# mcu.net
KiCad netlist of a schematic drawn in Altium Designer
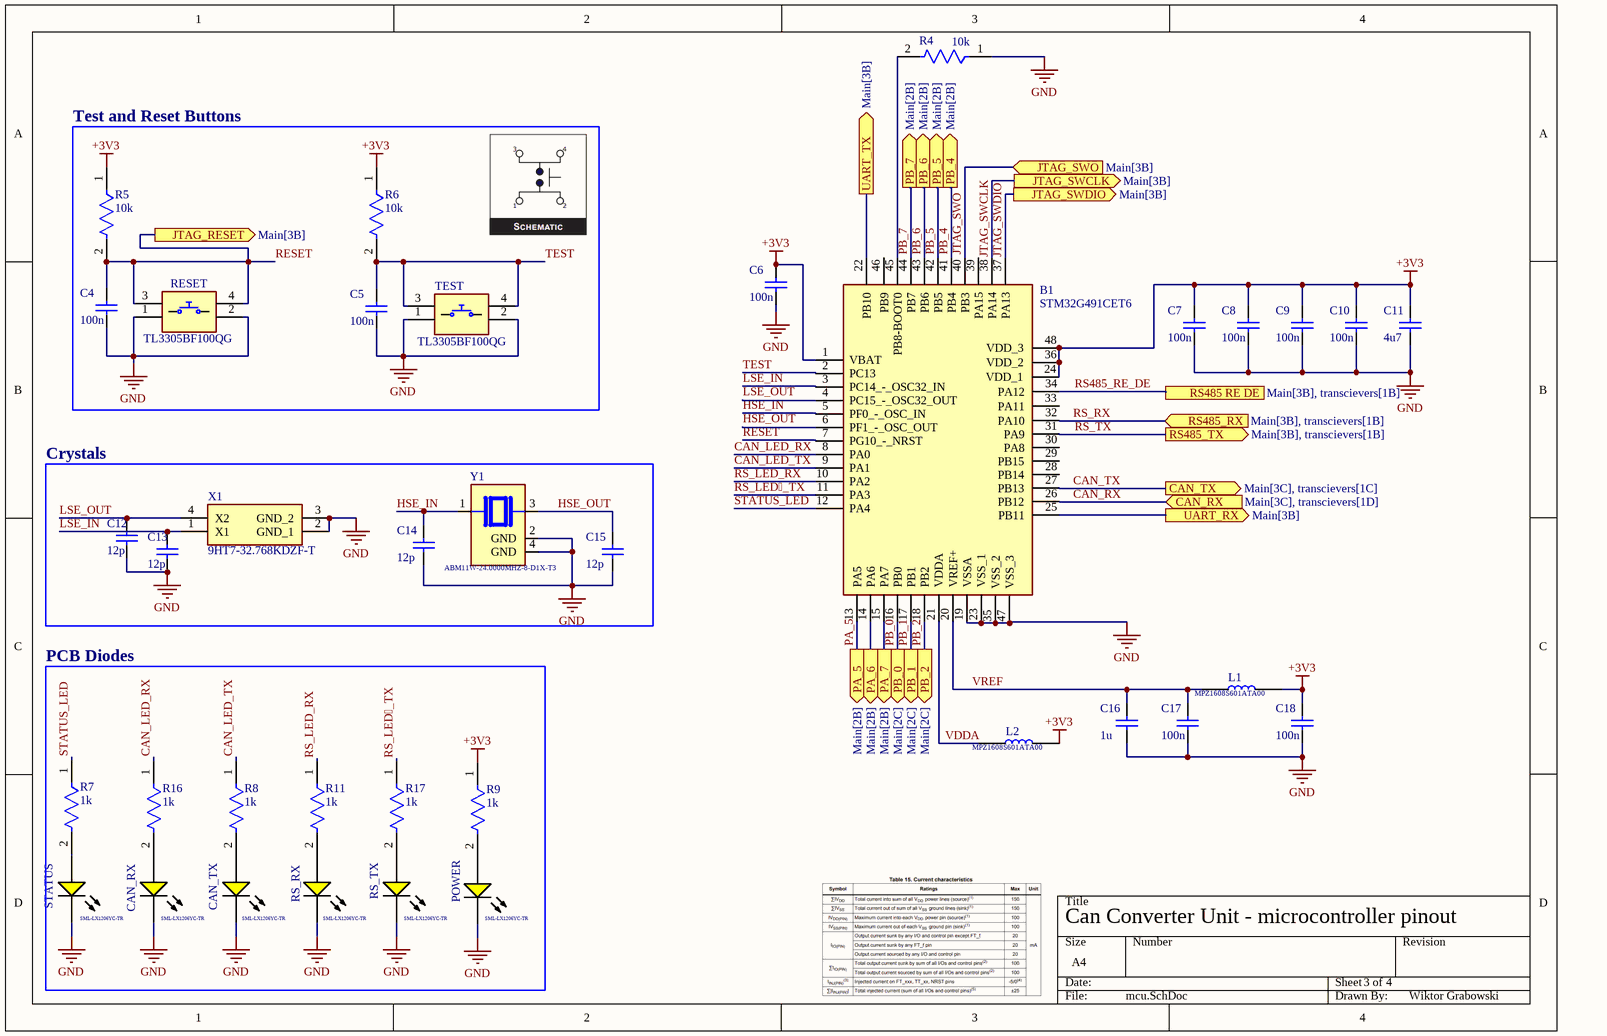
[diagram p0: mcu.SchDoc]

(export (version "E")
  (design (tool "Eeschema 10.0.6"))
  (components
    (comp (ref "B1")
      (value "STM32G491CET6")
      (footprint "STM32G491CET6")
      (description "ARM Microcontrollers - MCU Mainstream Arm Cortex-M4+ MCU 170MHz with 512Kbytes of Flash memory")
      (fields (field (name "MOUSER PART NUMBER") "511-STM32G491CET6"))
      (libsource (lib "HydrogreenLibrary") (part "STM32G491CET6"))
    )
    (comp (ref "C4")
      (value "100n")
      (footprint "CAPC1206(3216)170_M")
      (description "CAP 47nF 200V ±10% 1206 (3216 Metric) Thickness 1.7mm SMD")
      (fields (field (name "TOLERANCE") "Â±10%"))
      (libsource (lib "Altium Content Vault") (part "CAP"))
    )
    (comp (ref "C5")
      (value "100n")
      (footprint "CAPC1206(3216)170_M")
      (description "CAP 47nF 200V ±10% 1206 (3216 Metric) Thickness 1.7mm SMD")
      (fields (field (name "TOLERANCE") "Â±10%"))
      (libsource (lib "Altium Content Vault") (part "CAP"))
    )
    (comp (ref "C6")
      (value "100n")
      (footprint "CAPC1206(3216)170_M")
      (description "CAP 47nF 200V ±10% 1206 (3216 Metric) Thickness 1.7mm SMD")
      (fields (field (name "TOLERANCE") "Â±10%"))
      (libsource (lib "Altium Content Vault") (part "CAP"))
    )
    (comp (ref "C7")
      (value "100n")
      (footprint "CAPC1206(3216)170_M")
      (description "CAP 47nF 200V ±10% 1206 (3216 Metric) Thickness 1.7mm SMD")
      (fields (field (name "TOLERANCE") "Â±10%"))
      (libsource (lib "Altium Content Vault") (part "CAP"))
    )
    (comp (ref "C8")
      (value "100n")
      (footprint "CAPC1206(3216)170_M")
      (description "CAP 47nF 200V ±10% 1206 (3216 Metric) Thickness 1.7mm SMD")
      (fields (field (name "TOLERANCE") "Â±10%"))
      (libsource (lib "Altium Content Vault") (part "CAP"))
    )
    (comp (ref "C9")
      (value "100n")
      (footprint "CAPC1206(3216)170_M")
      (description "CAP 47nF 200V ±10% 1206 (3216 Metric) Thickness 1.7mm SMD")
      (fields (field (name "TOLERANCE") "Â±10%"))
      (libsource (lib "Altium Content Vault") (part "CAP"))
    )
    (comp (ref "C10")
      (value "100n")
      (footprint "CAPC1206(3216)170_M")
      (description "CAP 47nF 200V ±10% 1206 (3216 Metric) Thickness 1.7mm SMD")
      (fields (field (name "TOLERANCE") "Â±10%"))
      (libsource (lib "Altium Content Vault") (part "CAP"))
    )
    (comp (ref "C11")
      (value "4u7")
      (footprint "CAPC1206(3216)170_M")
      (description "CAP 47nF 200V ±10% 1206 (3216 Metric) Thickness 1.7mm SMD")
      (fields (field (name "TOLERANCE") "Â±10%"))
      (libsource (lib "Altium Content Vault") (part "CAP"))
    )
    (comp (ref "C12")
      (value "12p")
      (footprint "CAPC1206(3216)170_M")
      (description "CAP 47nF 200V ±10% 1206 (3216 Metric) Thickness 1.7mm SMD")
      (fields (field (name "TOLERANCE") "Â±10%"))
      (libsource (lib "Altium Content Vault") (part "CAP"))
    )
    (comp (ref "C13")
      (value "12p")
      (footprint "CAPC1206(3216)170_M")
      (description "CAP 47nF 200V ±10% 1206 (3216 Metric) Thickness 1.7mm SMD")
      (fields (field (name "TOLERANCE") "Â±10%"))
      (libsource (lib "Altium Content Vault") (part "CAP"))
    )
    (comp (ref "C14")
      (value "12p")
      (footprint "CAPC1206(3216)170_M")
      (description "CAP 47nF 200V ±10% 1206 (3216 Metric) Thickness 1.7mm SMD")
      (fields (field (name "TOLERANCE") "Â±10%"))
      (libsource (lib "Altium Content Vault") (part "CAP"))
    )
    (comp (ref "C15")
      (value "12p")
      (footprint "CAPC1206(3216)170_M")
      (description "CAP 47nF 200V ±10% 1206 (3216 Metric) Thickness 1.7mm SMD")
      (fields (field (name "TOLERANCE") "Â±10%"))
      (libsource (lib "Altium Content Vault") (part "CAP"))
    )
    (comp (ref "C16")
      (value "1u")
      (footprint "CAPC1206(3216)170_M")
      (description "CAP 47nF 200V ±10% 1206 (3216 Metric) Thickness 1.7mm SMD")
      (fields (field (name "TOLERANCE") "Â±10%"))
      (libsource (lib "Altium Content Vault") (part "CAP"))
    )
    (comp (ref "C17")
      (value "100n")
      (footprint "CAPC1206(3216)170_M")
      (description "CAP 47nF 200V ±10% 1206 (3216 Metric) Thickness 1.7mm SMD")
      (fields (field (name "TOLERANCE") "Â±10%"))
      (libsource (lib "Altium Content Vault") (part "CAP"))
    )
    (comp (ref "C18")
      (value "100n")
      (footprint "CAPC1206(3216)170_M")
      (description "CAP 47nF 200V ±10% 1206 (3216 Metric) Thickness 1.7mm SMD")
      (fields (field (name "TOLERANCE") "Â±10%"))
      (libsource (lib "Altium Content Vault") (part "CAP"))
    )
    (comp (ref "CAN_RX")
      (value "SML-LX1206YC-TR")
      (footprint "LUMX-SML-LX1206YC-TR_V")
      (description "Yellow LED, Water Clear Len, 585 nm, 2.1 V, -40 to 85 degC, 2-Pin SMD, RoHS, Tape and Reel")
      (fields (field (name "MANUFACTURER") "Lumex"))
      (libsource (lib "Altium Content Vault") (part "LED-YELLOW-AK-2"))
    )
    (comp (ref "CAN_TX")
      (value "SML-LX1206YC-TR")
      (footprint "LUMX-SML-LX1206YC-TR_V")
      (description "Yellow LED, Water Clear Len, 585 nm, 2.1 V, -40 to 85 degC, 2-Pin SMD, RoHS, Tape and Reel")
      (fields (field (name "MANUFACTURER") "Lumex"))
      (libsource (lib "Altium Content Vault") (part "LED-YELLOW-AK-2"))
    )
    (comp (ref "L1")
      (value "MPZ1608S601ATA00")
      (footprint "INDC1608X95N")
      (description "Ferrite Beads Multi-Layer 600Ohm 25% 100MHz 1A 0.15Ohm DCR 0603 T/R")
      (fields (field (name "MF") "TDK") (field (name "TOLERANCE") "25%"))
      (libsource (lib "HydrogreenLibrary") (part "MPZ1608S601ATA00"))
    )
    (comp (ref "L2")
      (value "MPZ1608S601ATA00")
      (footprint "INDC1608X95N")
      (description "Ferrite Beads Multi-Layer 600Ohm 25% 100MHz 1A 0.15Ohm DCR 0603 T/R")
      (fields (field (name "MF") "TDK") (field (name "TOLERANCE") "25%"))
      (libsource (lib "HydrogreenLibrary") (part "MPZ1608S601ATA00"))
    )
    (comp (ref "POWER")
      (value "SML-LX1206YC-TR")
      (footprint "LUMX-SML-LX1206YC-TR_V")
      (description "Yellow LED, Water Clear Len, 585 nm, 2.1 V, -40 to 85 degC, 2-Pin SMD, RoHS, Tape and Reel")
      (fields (field (name "MANUFACTURER") "Lumex"))
      (libsource (lib "Altium Content Vault") (part "LED-YELLOW-AK-2"))
    )
    (comp (ref "R4")
      (value "10k")
      (footprint "FP-RK73H2B-MFG")
      (description "40.2kΩ ±1% 0.25W Chip Resistor 1206 Thick Film AEC-Q200 Qualified")
      (fields (field (name "TOLERANCE") "1%"))
      (libsource (lib "Altium Content Vault") (part "1029c3af85768c4190bb7ad29bc67b5"))
    )
    (comp (ref "R5")
      (value "10k")
      (footprint "FP-RK73H2B-MFG")
      (description "40.2kΩ ±1% 0.25W Chip Resistor 1206 Thick Film AEC-Q200 Qualified")
      (fields (field (name "TOLERANCE") "1%"))
      (libsource (lib "Altium Content Vault") (part "1029c3af85768c4190bb7ad29bc67b5"))
    )
    (comp (ref "R6")
      (value "10k")
      (footprint "FP-RK73H2B-MFG")
      (description "40.2kΩ ±1% 0.25W Chip Resistor 1206 Thick Film AEC-Q200 Qualified")
      (fields (field (name "TOLERANCE") "1%"))
      (libsource (lib "Altium Content Vault") (part "1029c3af85768c4190bb7ad29bc67b5"))
    )
    (comp (ref "R7")
      (value "1k")
      (footprint "FP-RK73H2B-MFG")
      (description "40.2kΩ ±1% 0.25W Chip Resistor 1206 Thick Film AEC-Q200 Qualified")
      (fields (field (name "TOLERANCE") "1%"))
      (libsource (lib "Altium Content Vault") (part "1029c3af85768c4190bb7ad29bc67b5"))
    )
    (comp (ref "R8")
      (value "1k")
      (footprint "FP-RK73H2B-MFG")
      (description "40.2kΩ ±1% 0.25W Chip Resistor 1206 Thick Film AEC-Q200 Qualified")
      (fields (field (name "TOLERANCE") "1%"))
      (libsource (lib "Altium Content Vault") (part "1029c3af85768c4190bb7ad29bc67b5"))
    )
    (comp (ref "R9")
      (value "1k")
      (footprint "FP-RK73H2B-MFG")
      (description "40.2kΩ ±1% 0.25W Chip Resistor 1206 Thick Film AEC-Q200 Qualified")
      (fields (field (name "TOLERANCE") "1%"))
      (libsource (lib "Altium Content Vault") (part "1029c3af85768c4190bb7ad29bc67b5"))
    )
    (comp (ref "R11")
      (value "1k")
      (footprint "FP-RK73H2B-MFG")
      (description "40.2kΩ ±1% 0.25W Chip Resistor 1206 Thick Film AEC-Q200 Qualified")
      (fields (field (name "TOLERANCE") "1%"))
      (libsource (lib "Altium Content Vault") (part "1029c3af85768c4190bb7ad29bc67b5"))
    )
    (comp (ref "R16")
      (value "1k")
      (footprint "FP-RK73H2B-MFG")
      (description "40.2kΩ ±1% 0.25W Chip Resistor 1206 Thick Film AEC-Q200 Qualified")
      (fields (field (name "TOLERANCE") "1%"))
      (libsource (lib "Altium Content Vault") (part "1029c3af85768c4190bb7ad29bc67b5"))
    )
    (comp (ref "R17")
      (value "1k")
      (footprint "FP-RK73H2B-MFG")
      (description "40.2kΩ ±1% 0.25W Chip Resistor 1206 Thick Film AEC-Q200 Qualified")
      (fields (field (name "TOLERANCE") "1%"))
      (libsource (lib "Altium Content Vault") (part "1029c3af85768c4190bb7ad29bc67b5"))
    )
    (comp (ref "RESET")
      (value "TL3305BF100QG")
      (footprint "TL3305BF160QG")
      (description "TL3305 Ultra-Miniature Tact Switch 100gf 5.0mm actuator Silver Contact Gullwing")
      (fields
        (field (name "MOUSER PART NUMBER") "612-TL3305BF100QG")
        (field (name "MANUFACTURER") "E-Switch")
      )
      (libsource (lib "HydrogreenLibrary") (part "TL3305BF100QG"))
    )
    (comp (ref "RS_RX")
      (value "SML-LX1206YC-TR")
      (footprint "LUMX-SML-LX1206YC-TR_V")
      (description "Yellow LED, Water Clear Len, 585 nm, 2.1 V, -40 to 85 degC, 2-Pin SMD, RoHS, Tape and Reel")
      (fields (field (name "MANUFACTURER") "Lumex"))
      (libsource (lib "Altium Content Vault") (part "LED-YELLOW-AK-2"))
    )
    (comp (ref "RS_TX")
      (value "SML-LX1206YC-TR")
      (footprint "LUMX-SML-LX1206YC-TR_V")
      (description "Yellow LED, Water Clear Len, 585 nm, 2.1 V, -40 to 85 degC, 2-Pin SMD, RoHS, Tape and Reel")
      (fields (field (name "MANUFACTURER") "Lumex"))
      (libsource (lib "Altium Content Vault") (part "LED-YELLOW-AK-2"))
    )
    (comp (ref "STATUS")
      (value "SML-LX1206YC-TR")
      (footprint "LUMX-SML-LX1206YC-TR_V")
      (description "Yellow LED, Water Clear Len, 585 nm, 2.1 V, -40 to 85 degC, 2-Pin SMD, RoHS, Tape and Reel")
      (fields (field (name "MANUFACTURER") "Lumex"))
      (libsource (lib "Altium Content Vault") (part "LED-YELLOW-AK-2"))
    )
    (comp (ref "TEST")
      (value "TL3305BF100QG")
      (footprint "TL3305BF160QG")
      (description "TL3305 Ultra-Miniature Tact Switch 100gf 5.0mm actuator Silver Contact Gullwing")
      (fields
        (field (name "MOUSER PART NUMBER") "612-TL3305BF100QG")
        (field (name "MANUFACTURER") "E-Switch")
      )
      (libsource (lib "HydrogreenLibrary") (part "TL3305BF100QG"))
    )
    (comp (ref "X1")
      (value "9HT7-32.768KDZF-T")
      (footprint "9HT732768KDZFT")
      (description "Parallel - Fundamental Quartz Crystal, 0.032768MHz Nom")
      (fields (field (name "MOUSER PART NUMBER") "717-9HT7-32.768KDZFT") (field (name "MANUFACTURER") "TXC"))
      (libsource (lib "HydrogreenLibrary") (part "9HT7-32.768KDZF-T"))
    )
    (comp (ref "Y1")
      (value "ABM11W-24.0000MHZ-8-D1X-T3")
      (footprint "XTAL_ABM11W-24.0000MHZ-8-D1X-T3")
      (description "Crystal, Quartz, 24 MHz, SMD, 2mm x 1.6mm x 0.5mm, 20 ppm, 8 pF, 10 ppm, ABM11W")
      (fields (field (name "MF") "Abracon LLC") (field (name "MANUFACTURER") "Abracon"))
      (libsource (lib "HydrogreenLibrary") (part "ABM11W-24.0000MHZ-8-D1X-T3"))
    )
  )
  (nets
    (net (code "1") (name "+3V3") (class "Default")
      (node (ref "B1") (pin "1") (pinfunction "VBAT_1") (pintype "passive"))
      (node (ref "B1") (pin "24") (pinfunction "VDD_1_24") (pintype "passive"))
      (node (ref "B1") (pin "36") (pinfunction "VDD_2_36") (pintype "passive"))
      (node (ref "B1") (pin "48") (pinfunction "VDD_3_48") (pintype "passive"))
      (node (ref "C10") (pin "2") (pinfunction "2_2") (pintype "passive"))
      (node (ref "C11") (pin "2") (pinfunction "2_2") (pintype "passive"))
      (node (ref "C18") (pin "2") (pinfunction "2_2") (pintype "passive"))
      (node (ref "C6") (pin "2") (pinfunction "2_2") (pintype "passive"))
      (node (ref "C7") (pin "2") (pinfunction "2_2") (pintype "passive"))
      (node (ref "C8") (pin "2") (pinfunction "2_2") (pintype "passive"))
      (node (ref "C9") (pin "2") (pinfunction "2_2") (pintype "passive"))
      (node (ref "L1") (pin "2") (pinfunction "2_2") (pintype "passive"))
      (node (ref "L2") (pin "2") (pinfunction "2_2") (pintype "passive"))
      (node (ref "R5") (pin "1") (pinfunction "1_1") (pintype "passive"))
      (node (ref "R6") (pin "1") (pinfunction "1_1") (pintype "passive"))
      (node (ref "R9") (pin "1") (pinfunction "1_1") (pintype "passive"))
    )
    (net (code "2") (name "/CAN_LED_RX") (class "Default")
      (node (ref "B1") (pin "8") (pinfunction "PA0_8") (pintype "passive"))
      (node (ref "R16") (pin "1") (pinfunction "1_1") (pintype "passive"))
    )
    (net (code "3") (name "/CAN_LED_TX") (class "Default")
      (node (ref "B1") (pin "9") (pinfunction "PA1_9") (pintype "passive"))
      (node (ref "R8") (pin "1") (pinfunction "1_1") (pintype "passive"))
    )
    (net (code "4") (name "/CAN_RX") (class "Default")
      (node (ref "B1") (pin "26") (pinfunction "PB12_26") (pintype "passive"))
    )
    (net (code "5") (name "/CAN_TX") (class "Default")
      (node (ref "B1") (pin "27") (pinfunction "PB13_27") (pintype "passive"))
    )
    (net (code "6") (name "/HSE_IN") (class "Default")
      (node (ref "B1") (pin "5") (pinfunction "PF0_-_OSC_IN_5") (pintype "passive"))
      (node (ref "C14") (pin "2") (pinfunction "2_2") (pintype "passive"))
      (node (ref "Y1") (pin "1") (pinfunction "1_1") (pintype "passive"))
    )
    (net (code "7") (name "/HSE_OUT") (class "Default")
      (node (ref "B1") (pin "6") (pinfunction "PF1_-_OSC_OUT_6") (pintype "passive"))
      (node (ref "C15") (pin "2") (pinfunction "2_2") (pintype "passive"))
      (node (ref "Y1") (pin "3") (pinfunction "2_3") (pintype "passive"))
    )
    (net (code "8") (name "/JTAG_SWCLK") (class "Default")
      (node (ref "B1") (pin "38") (pinfunction "PA14_38") (pintype "passive"))
    )
    (net (code "9") (name "/JTAG_SWDIO") (class "Default")
      (node (ref "B1") (pin "37") (pinfunction "PA13_37") (pintype "passive"))
    )
    (net (code "10") (name "/JTAG_SWO") (class "Default")
      (node (ref "B1") (pin "40") (pinfunction "PB3_40") (pintype "passive"))
    )
    (net (code "11") (name "/LSE_IN") (class "Default")
      (node (ref "B1") (pin "3") (pinfunction "PC14_-_OSC32_IN_3") (pintype "passive"))
      (node (ref "C13") (pin "2") (pinfunction "2_2") (pintype "passive"))
      (node (ref "X1") (pin "1") (pinfunction "X1_1") (pintype "passive"))
    )
    (net (code "12") (name "/LSE_OUT") (class "Default")
      (node (ref "B1") (pin "4") (pinfunction "PC15_-_OSC32_OUT_4") (pintype "passive"))
      (node (ref "C12") (pin "2") (pinfunction "2_2") (pintype "passive"))
      (node (ref "X1") (pin "4") (pinfunction "X2_4") (pintype "passive"))
    )
    (net (code "13") (name "/PA_5") (class "Default")
      (node (ref "B1") (pin "13") (pinfunction "PA5_13") (pintype "passive"))
    )
    (net (code "14") (name "/PA_6") (class "Default")
      (node (ref "B1") (pin "14") (pinfunction "PA6_14") (pintype "passive"))
    )
    (net (code "15") (name "/PA_7") (class "Default")
      (node (ref "B1") (pin "15") (pinfunction "PA7_15") (pintype "passive"))
    )
    (net (code "16") (name "/PB_0") (class "Default")
      (node (ref "B1") (pin "16") (pinfunction "PB0_16") (pintype "passive"))
    )
    (net (code "17") (name "/PB_1") (class "Default")
      (node (ref "B1") (pin "17") (pinfunction "PB1_17") (pintype "passive"))
    )
    (net (code "18") (name "/PB_2") (class "Default")
      (node (ref "B1") (pin "18") (pinfunction "PB2_18") (pintype "passive"))
    )
    (net (code "19") (name "/PB_4") (class "Default")
      (node (ref "B1") (pin "41") (pinfunction "PB4_41") (pintype "passive"))
    )
    (net (code "20") (name "/PB_5") (class "Default")
      (node (ref "B1") (pin "42") (pinfunction "PB5_42") (pintype "passive"))
    )
    (net (code "21") (name "/PB_6") (class "Default")
      (node (ref "B1") (pin "43") (pinfunction "PB6_43") (pintype "passive"))
    )
    (net (code "22") (name "/PB_7") (class "Default")
      (node (ref "B1") (pin "44") (pinfunction "PB7_44") (pintype "passive"))
    )
    (net (code "23") (name "/RESET") (class "Default")
      (node (ref "B1") (pin "7") (pinfunction "PG10_-_NRST_7") (pintype "passive"))
      (node (ref "C4") (pin "2") (pinfunction "2_2") (pintype "passive"))
      (node (ref "R5") (pin "2") (pinfunction "2_2") (pintype "passive"))
      (node (ref "RESET") (pin "3") (pintype "passive"))
      (node (ref "RESET") (pin "4") (pintype "passive"))
    )
    (net (code "24") (name "/RS485_RE_DE") (class "Default")
      (node (ref "B1") (pin "34") (pinfunction "PA12_34") (pintype "passive"))
    )
    (net (code "25") (name "/RS_LED_TX") (class "Default")
      (node (ref "B1") (pin "11") (pinfunction "PA3_11") (pintype "passive"))
      (node (ref "R17") (pin "1") (pinfunction "1_1") (pintype "passive"))
    )
    (net (code "26") (name "/RS_LED_RX") (class "Default")
      (node (ref "B1") (pin "10") (pinfunction "PA2_10") (pintype "passive"))
      (node (ref "R11") (pin "1") (pinfunction "1_1") (pintype "passive"))
    )
    (net (code "27") (name "/RS_RX") (class "Default")
      (node (ref "B1") (pin "32") (pinfunction "PA10_32") (pintype "passive"))
    )
    (net (code "28") (name "/RS_TX") (class "Default")
      (node (ref "B1") (pin "31") (pinfunction "PA9_31") (pintype "passive"))
    )
    (net (code "29") (name "/STATUS_LED") (class "Default")
      (node (ref "B1") (pin "12") (pinfunction "PA4_12") (pintype "passive"))
      (node (ref "R7") (pin "1") (pinfunction "1_1") (pintype "passive"))
    )
    (net (code "30") (name "/TEST") (class "Default")
      (node (ref "B1") (pin "2") (pinfunction "PC13_2") (pintype "passive"))
      (node (ref "C5") (pin "2") (pinfunction "2_2") (pintype "passive"))
      (node (ref "R6") (pin "2") (pinfunction "2_2") (pintype "passive"))
      (node (ref "TEST") (pin "3") (pintype "passive"))
      (node (ref "TEST") (pin "4") (pintype "passive"))
    )
    (net (code "31") (name "/UART_RX") (class "Default")
      (node (ref "B1") (pin "25") (pinfunction "PB11_25") (pintype "passive"))
    )
    (net (code "32") (name "/UART_TX") (class "Default")
      (node (ref "B1") (pin "22") (pinfunction "PB10_22") (pintype "passive"))
    )
    (net (code "33") (name "/VDDA") (class "Default")
      (node (ref "B1") (pin "21") (pinfunction "VDDA_21") (pintype "passive"))
      (node (ref "L2") (pin "1") (pinfunction "1_1") (pintype "passive"))
    )
    (net (code "34") (name "/VREF") (class "Default")
      (node (ref "B1") (pin "20") (pinfunction "VREF+_20") (pintype "passive"))
      (node (ref "C16") (pin "2") (pinfunction "2_2") (pintype "passive"))
      (node (ref "C17") (pin "2") (pinfunction "2_2") (pintype "passive"))
      (node (ref "L1") (pin "1") (pinfunction "1_1") (pintype "passive"))
    )
    (net (code "35") (name "GND") (class "Default")
      (node (ref "B1") (pin "19") (pinfunction "VSSA_19") (pintype "passive"))
      (node (ref "B1") (pin "23") (pinfunction "VSS_1_23") (pintype "passive"))
      (node (ref "B1") (pin "35") (pinfunction "VSS_2_35") (pintype "passive"))
      (node (ref "B1") (pin "47") (pinfunction "VSS_3_47") (pintype "passive"))
      (node (ref "C10") (pin "1") (pinfunction "1_1") (pintype "passive"))
      (node (ref "C11") (pin "1") (pinfunction "1_1") (pintype "passive"))
      (node (ref "C12") (pin "1") (pinfunction "1_1") (pintype "passive"))
      (node (ref "C13") (pin "1") (pinfunction "1_1") (pintype "passive"))
      (node (ref "C14") (pin "1") (pinfunction "1_1") (pintype "passive"))
      (node (ref "C15") (pin "1") (pinfunction "1_1") (pintype "passive"))
      (node (ref "C16") (pin "1") (pinfunction "1_1") (pintype "passive"))
      (node (ref "C17") (pin "1") (pinfunction "1_1") (pintype "passive"))
      (node (ref "C18") (pin "1") (pinfunction "1_1") (pintype "passive"))
      (node (ref "C4") (pin "1") (pinfunction "1_1") (pintype "passive"))
      (node (ref "C5") (pin "1") (pinfunction "1_1") (pintype "passive"))
      (node (ref "C6") (pin "1") (pinfunction "1_1") (pintype "passive"))
      (node (ref "C7") (pin "1") (pinfunction "1_1") (pintype "passive"))
      (node (ref "C8") (pin "1") (pinfunction "1_1") (pintype "passive"))
      (node (ref "C9") (pin "1") (pinfunction "1_1") (pintype "passive"))
      (node (ref "CAN_RX") (pin "2") (pinfunction "K_2") (pintype "passive"))
      (node (ref "CAN_TX") (pin "2") (pinfunction "K_2") (pintype "passive"))
      (node (ref "POWER") (pin "2") (pinfunction "K_2") (pintype "passive"))
      (node (ref "R4") (pin "1") (pinfunction "1_1") (pintype "passive"))
      (node (ref "RESET") (pin "1") (pintype "passive"))
      (node (ref "RESET") (pin "2") (pintype "passive"))
      (node (ref "RS_RX") (pin "2") (pinfunction "K_2") (pintype "passive"))
      (node (ref "RS_TX") (pin "2") (pinfunction "K_2") (pintype "passive"))
      (node (ref "STATUS") (pin "2") (pinfunction "K_2") (pintype "passive"))
      (node (ref "TEST") (pin "1") (pintype "passive"))
      (node (ref "TEST") (pin "2") (pintype "passive"))
      (node (ref "X1") (pin "2") (pinfunction "GND_1_2") (pintype "passive"))
      (node (ref "X1") (pin "3") (pinfunction "GND_2_3") (pintype "passive"))
      (node (ref "Y1") (pin "2") (pinfunction "GND_2") (pintype "power_in"))
      (node (ref "Y1") (pin "4") (pinfunction "GND_4") (pintype "power_in"))
    )
    (net (code "36") (name "Net-(B1-PB8-BOOT0)") (class "Default")
      (node (ref "B1") (pin "45") (pinfunction "PB8-BOOT0_45") (pintype "passive"))
      (node (ref "R4") (pin "2") (pinfunction "2_2") (pintype "passive"))
    )
    (net (code "37") (name "Net-(CAN_RX-A)") (class "Default")
      (node (ref "CAN_RX") (pin "1") (pinfunction "A_1") (pintype "passive"))
      (node (ref "R16") (pin "2") (pinfunction "2_2") (pintype "passive"))
    )
    (net (code "38") (name "Net-(CAN_TX-A)") (class "Default")
      (node (ref "CAN_TX") (pin "1") (pinfunction "A_1") (pintype "passive"))
      (node (ref "R8") (pin "2") (pinfunction "2_2") (pintype "passive"))
    )
    (net (code "39") (name "Net-(POWER-A)") (class "Default")
      (node (ref "POWER") (pin "1") (pinfunction "A_1") (pintype "passive"))
      (node (ref "R9") (pin "2") (pinfunction "2_2") (pintype "passive"))
    )
    (net (code "40") (name "Net-(RS_RX-A)") (class "Default")
      (node (ref "R11") (pin "2") (pinfunction "2_2") (pintype "passive"))
      (node (ref "RS_RX") (pin "1") (pinfunction "A_1") (pintype "passive"))
    )
    (net (code "41") (name "Net-(RS_TX-A)") (class "Default")
      (node (ref "R17") (pin "2") (pinfunction "2_2") (pintype "passive"))
      (node (ref "RS_TX") (pin "1") (pinfunction "A_1") (pintype "passive"))
    )
    (net (code "42") (name "Net-(STATUS-A)") (class "Default")
      (node (ref "R7") (pin "2") (pinfunction "2_2") (pintype "passive"))
      (node (ref "STATUS") (pin "1") (pinfunction "A_1") (pintype "passive"))
    )
    (net (code "43") (name "unconnected-(B1-PA8-Pad30)") (class "Default")
      (node (ref "B1") (pin "30") (pinfunction "PA8_30") (pintype "passive"))
    )
    (net (code "44") (name "unconnected-(B1-PA11-Pad33)") (class "Default")
      (node (ref "B1") (pin "33") (pinfunction "PA11_33") (pintype "passive"))
    )
    (net (code "45") (name "unconnected-(B1-PA15-Pad39)") (class "Default")
      (node (ref "B1") (pin "39") (pinfunction "PA15_39") (pintype "passive"))
    )
    (net (code "46") (name "unconnected-(B1-PB9-Pad46)") (class "Default")
      (node (ref "B1") (pin "46") (pinfunction "PB9_46") (pintype "passive"))
    )
    (net (code "47") (name "unconnected-(B1-PB14-Pad28)") (class "Default")
      (node (ref "B1") (pin "28") (pinfunction "PB14_28") (pintype "passive"))
    )
    (net (code "48") (name "unconnected-(B1-PB15-Pad29)") (class "Default")
      (node (ref "B1") (pin "29") (pinfunction "PB15_29") (pintype "passive"))
    )
  )
)
